# exixe_pogo.net
KiCad netlist of a schematic drawn in EAGLE
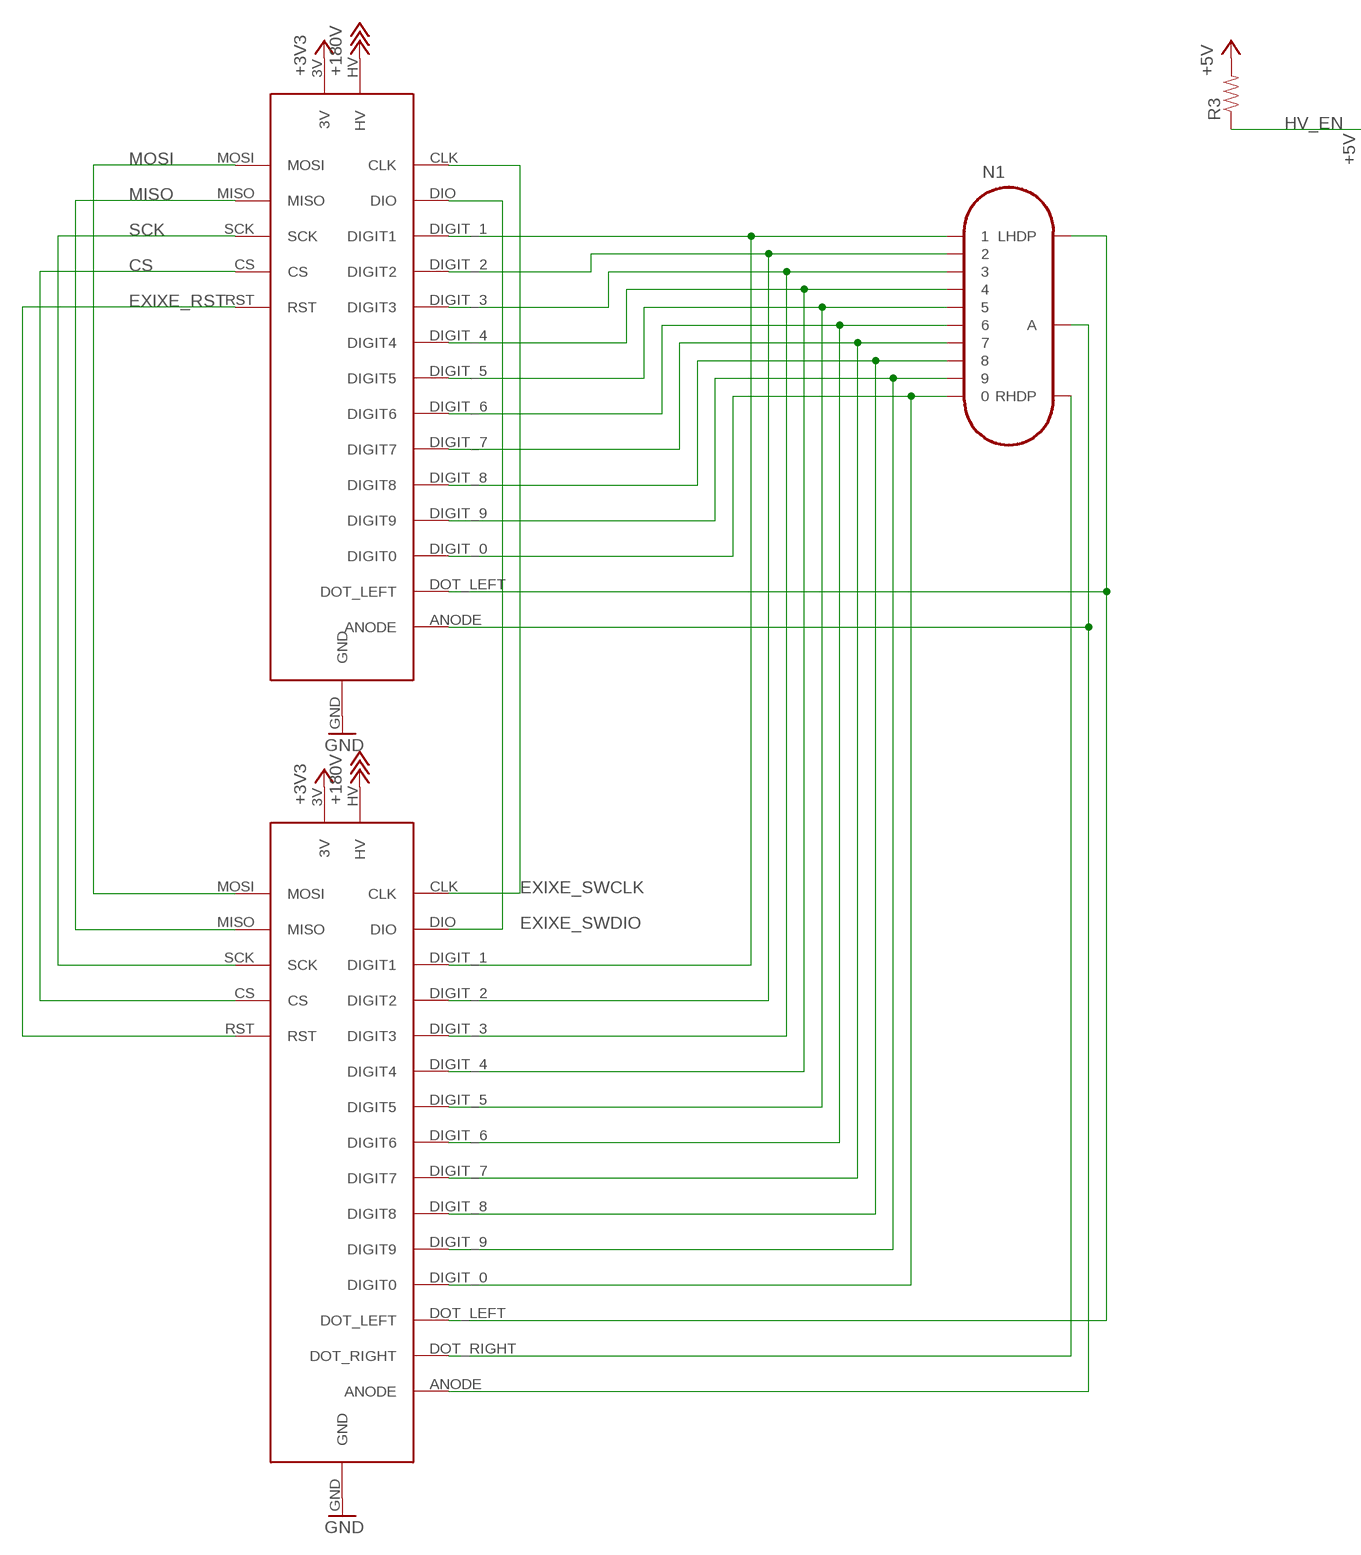
[diagram p0: schematic, sheet 1, part 1 of 2]
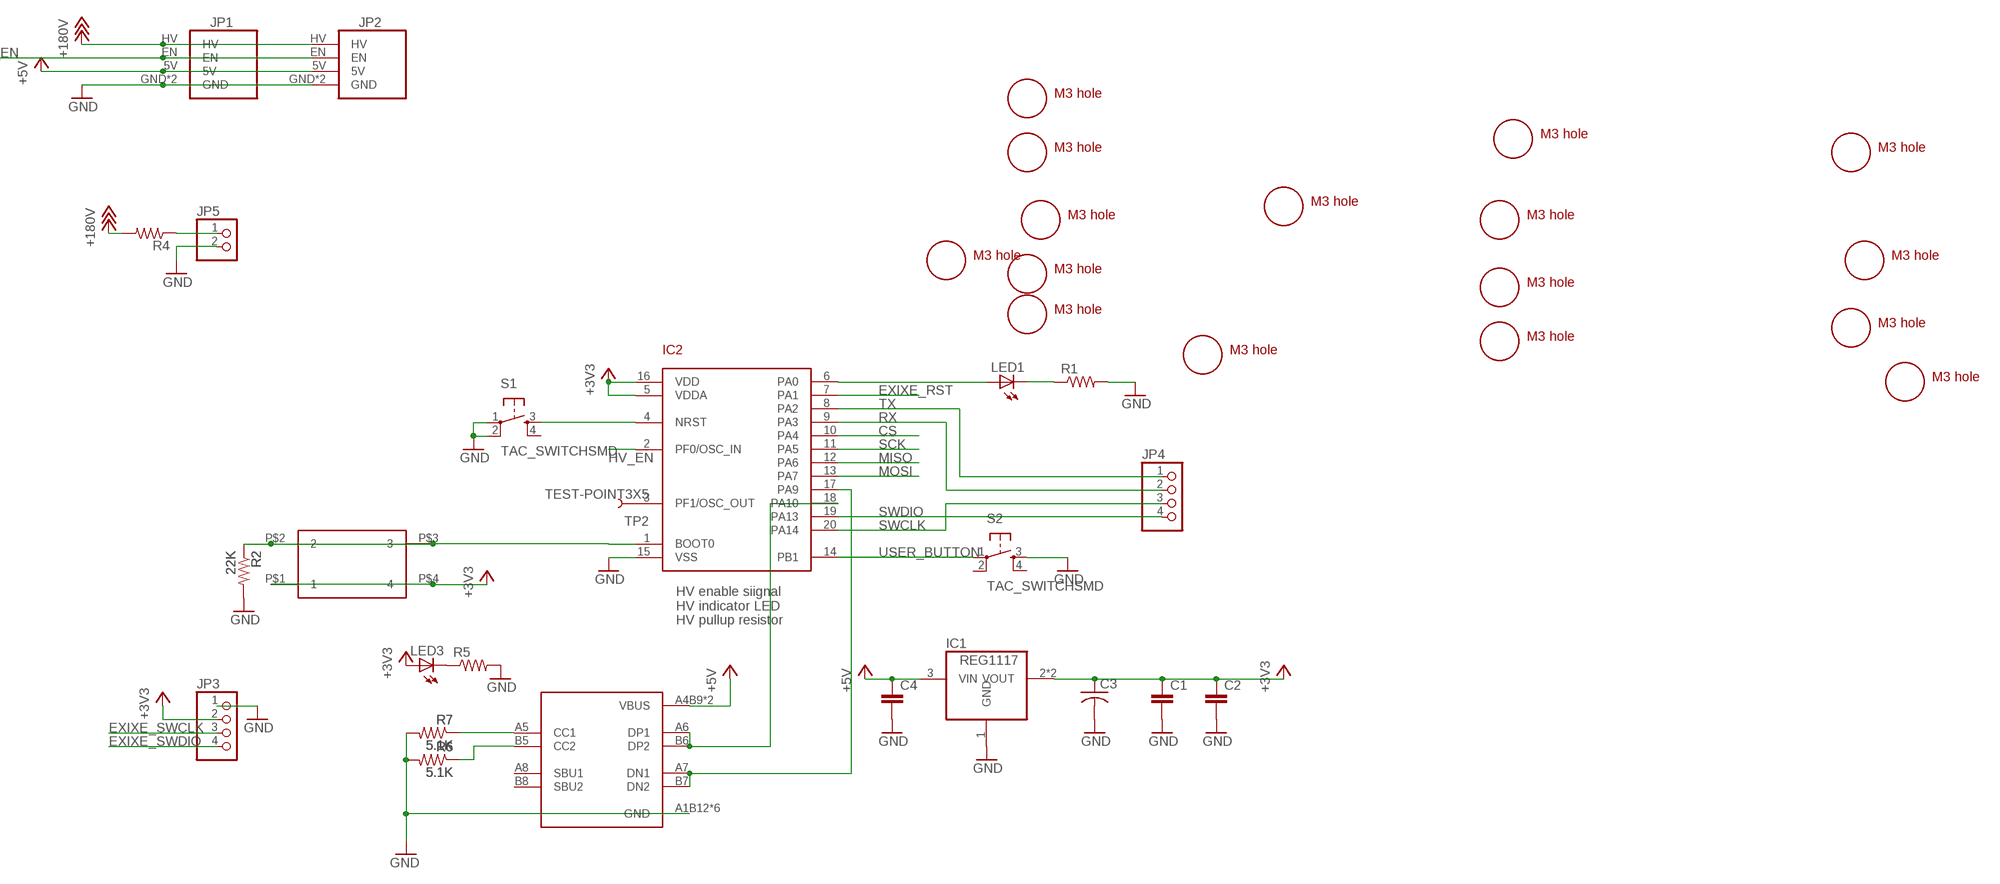
[diagram p1: schematic, sheet 1, part 2 of 2]

(export (version "E")
  (design (tool "Eeschema 10.0.6"))
  (components
    (comp (ref "C1")
      (value "CAP0805")
      (footprint "eagle-import:0805")
      (libsource (lib "eagle-import") (part "CAP0805"))
    )
    (comp (ref "C2")
      (value "CAP0805")
      (footprint "eagle-import:0805")
      (libsource (lib "eagle-import") (part "CAP0805"))
    )
    (comp (ref "C3")
      (value "C-USC1210")
      (footprint "eagle-import:C1210")
      (libsource (lib "eagle-import") (part "C-USC1210"))
    )
    (comp (ref "C4")
      (value "CAP0805")
      (footprint "eagle-import:0805")
      (libsource (lib "eagle-import") (part "CAP0805"))
    )
    (comp (ref "IC1")
      (value "REG1117")
      (footprint "eagle-import:SOT223")
      (libsource (lib "eagle-import") (part "REG1117"))
    )
    (comp (ref "IC2")
      (value "STM32F030F4")
      (footprint "eagle-import:TSSOP20")
      (libsource (lib "eagle-import") (part "STM32F030F4"))
    )
    (comp (ref "JP1")
      (value "EBAY_MODULEEBAY")
      (footprint "eagle-import:EBAY_PKG")
      (libsource (lib "eagle-import") (part "EBAY_MODULEEBAY"))
    )
    (comp (ref "JP2")
      (value "EBAY_MODULETAOBAO")
      (footprint "eagle-import:TAOBAO_PKG")
      (libsource (lib "eagle-import") (part "EBAY_MODULETAOBAO"))
    )
    (comp (ref "JP3")
      (value "PINHD-1X4")
      (footprint "eagle-import:1X04")
      (libsource (lib "eagle-import") (part "PINHD-1X4"))
    )
    (comp (ref "JP4")
      (value "PINHD-1X4")
      (footprint "eagle-import:1X04")
      (libsource (lib "eagle-import") (part "PINHD-1X4"))
    )
    (comp (ref "JP5")
      (value "PINHD-1X2")
      (footprint "eagle-import:1X02")
      (libsource (lib "eagle-import") (part "PINHD-1X2"))
    )
    (comp (ref "LED1")
      (value "LEDCHIP-LED0805")
      (footprint "eagle-import:CHIP-LED0805")
      (libsource (lib "eagle-import") (part "LEDCHIP-LED0805"))
    )
    (comp (ref "LED3")
      (value "LEDCHIP-LED0805")
      (footprint "eagle-import:CHIP-LED0805")
      (libsource (lib "eagle-import") (part "LEDCHIP-LED0805"))
    )
    (comp (ref "N1")
      (value "IN-14")
      (footprint "eagle-import:IN-14")
      (libsource (lib "eagle-import") (part "IN-14"))
    )
    (comp (ref "R1")
      (value "RESISTOR0805-RES")
      (footprint "eagle-import:0805")
      (libsource (lib "eagle-import") (part "RESISTOR0805-RES"))
    )
    (comp (ref "R2")
      (value "22K")
      (footprint "eagle-import:0805")
      (libsource (lib "eagle-import") (part "joyAnalog_RESISTOR0805-RES"))
    )
    (comp (ref "R3")
      (value "RESISTOR0805-RES")
      (footprint "eagle-import:0805")
      (libsource (lib "eagle-import") (part "RESISTOR0805-RES"))
    )
    (comp (ref "R4")
      (value "RESISTOR0805-RES")
      (footprint "eagle-import:0805")
      (libsource (lib "eagle-import") (part "RESISTOR0805-RES"))
    )
    (comp (ref "R5")
      (value "RESISTOR0805-RES")
      (footprint "eagle-import:0805")
      (libsource (lib "eagle-import") (part "RESISTOR0805-RES"))
    )
    (comp (ref "R6")
      (value "5.1K")
      (footprint "eagle-import:0805")
      (libsource (lib "eagle-import") (part "joyAnalog_RESISTOR0805-RES"))
    )
    (comp (ref "R7")
      (value "5.1K")
      (footprint "eagle-import:0805")
      (libsource (lib "eagle-import") (part "joyAnalog_RESISTOR0805-RES"))
    )
    (comp (ref "S1")
      (value "TAC_SWITCHSMD")
      (footprint "eagle-import:TACTILE-SWITCH-SMD")
      (libsource (lib "eagle-import") (part "TAC_SWITCHSMD"))
    )
    (comp (ref "S2")
      (value "TAC_SWITCHSMD")
      (footprint "eagle-import:TACTILE-SWITCH-SMD")
      (libsource (lib "eagle-import") (part "TAC_SWITCHSMD"))
    )
    (comp (ref "SW2")
      (value "324_SW324_SWITCH_FOOT_HOLE")
      (footprint "eagle-import:342_SWICH_FOOT_HOLE")
      (libsource (lib "eagle-import") (part "324_SW324_SWITCH_FOOT_HOLE"))
    )
    (comp (ref "TP2")
      (value "TEST-POINT3X5")
      (footprint "eagle-import:PAD.03X.05")
      (libsource (lib "eagle-import") (part "TEST-POINT3X5"))
    )
    (comp (ref "U$1")
      (value "EXIXE12_POGO")
      (footprint "eagle-import:EXIXE12_PAC")
      (libsource (lib "eagle-import") (part "EXIXE12_POGO"))
    )
    (comp (ref "U$2")
      (value "EXIXE14_POGO")
      (footprint "eagle-import:EXIXE14_PAC")
      (libsource (lib "eagle-import") (part "EXIXE14_POGO"))
    )
    (comp (ref "U$3")
      (value "M3_MOUNTING_HOLE")
      (footprint "eagle-import:M3_MOUNTING_HOLE_PACK")
      (libsource (lib "eagle-import") (part "M3_MOUNTING_HOLE"))
    )
    (comp (ref "U$4")
      (value "M3_MOUNTING_HOLE")
      (footprint "eagle-import:M3_MOUNTING_HOLE_PACK")
      (libsource (lib "eagle-import") (part "M3_MOUNTING_HOLE"))
    )
    (comp (ref "U$5")
      (value "M3_MOUNTING_HOLE")
      (footprint "eagle-import:M3_MOUNTING_HOLE_PACK")
      (libsource (lib "eagle-import") (part "M3_MOUNTING_HOLE"))
    )
    (comp (ref "U$6")
      (value "M3_MOUNTING_HOLE")
      (footprint "eagle-import:M3_MOUNTING_HOLE_PACK")
      (libsource (lib "eagle-import") (part "M3_MOUNTING_HOLE"))
    )
    (comp (ref "U$7")
      (value "M3_MOUNTING_HOLE")
      (footprint "eagle-import:M3_MOUNTING_HOLE_PACK")
      (libsource (lib "eagle-import") (part "M3_MOUNTING_HOLE"))
    )
    (comp (ref "U$8")
      (value "M3_MOUNTING_HOLE")
      (footprint "eagle-import:M3_MOUNTING_HOLE_PACK")
      (libsource (lib "eagle-import") (part "M3_MOUNTING_HOLE"))
    )
    (comp (ref "U$9")
      (value "M3_MOUNTING_HOLE")
      (footprint "eagle-import:M3_MOUNTING_HOLE_PACK")
      (libsource (lib "eagle-import") (part "M3_MOUNTING_HOLE"))
    )
    (comp (ref "U$10")
      (value "M3_MOUNTING_HOLE")
      (footprint "eagle-import:M3_MOUNTING_HOLE_PACK")
      (libsource (lib "eagle-import") (part "M3_MOUNTING_HOLE"))
    )
    (comp (ref "U$11")
      (value "M3_MOUNTING_HOLE")
      (footprint "eagle-import:M3_MOUNTING_HOLE_PACK")
      (libsource (lib "eagle-import") (part "M3_MOUNTING_HOLE"))
    )
    (comp (ref "U$12")
      (value "M3_MOUNTING_HOLE")
      (footprint "eagle-import:M3_MOUNTING_HOLE_PACK")
      (libsource (lib "eagle-import") (part "M3_MOUNTING_HOLE"))
    )
    (comp (ref "U$13")
      (value "M3_MOUNTING_HOLE")
      (footprint "eagle-import:M3_MOUNTING_HOLE_PACK")
      (libsource (lib "eagle-import") (part "M3_MOUNTING_HOLE"))
    )
    (comp (ref "U$14")
      (value "M3_MOUNTING_HOLE")
      (footprint "eagle-import:M3_MOUNTING_HOLE_PACK")
      (libsource (lib "eagle-import") (part "M3_MOUNTING_HOLE"))
    )
    (comp (ref "U$15")
      (value "M3_MOUNTING_HOLE")
      (footprint "eagle-import:M3_MOUNTING_HOLE_PACK")
      (libsource (lib "eagle-import") (part "M3_MOUNTING_HOLE"))
    )
    (comp (ref "U$16")
      (value "M3_MOUNTING_HOLE")
      (footprint "eagle-import:M3_MOUNTING_HOLE_PACK")
      (libsource (lib "eagle-import") (part "M3_MOUNTING_HOLE"))
    )
    (comp (ref "U$17")
      (value "M3_MOUNTING_HOLE")
      (footprint "eagle-import:M3_MOUNTING_HOLE_PACK")
      (libsource (lib "eagle-import") (part "M3_MOUNTING_HOLE"))
    )
    (comp (ref "U$18")
      (value "M3_MOUNTING_HOLE")
      (footprint "eagle-import:M3_MOUNTING_HOLE_PACK")
      (libsource (lib "eagle-import") (part "M3_MOUNTING_HOLE"))
    )
    (comp (ref "U1")
      (value "USBC_16P_CENTERED")
      (footprint "eagle-import:USBC_16P_FOOT")
      (libsource (lib "eagle-import") (part "USBC_16P_CENTERED"))
    )
  )
  (nets
    (net (code "1") (name "+3V3") (class "Default")
      (node (ref "C1") (pin "1") (pinfunction "1_1") (pintype "passive"))
      (node (ref "C2") (pin "1") (pinfunction "1_1") (pintype "passive"))
      (node (ref "C3") (pin "1") (pinfunction "1_1") (pintype "passive"))
      (node (ref "IC1") (pin "2") (pinfunction "VOUT_2") (pintype "output"))
      (node (ref "IC1") (pin "4") (pinfunction "VOUT_4") (pintype "output"))
      (node (ref "IC2") (pin "16") (pinfunction "VDD_16") (pintype "bidirectional"))
      (node (ref "IC2") (pin "5") (pinfunction "VDDA_5") (pintype "bidirectional"))
      (node (ref "JP3") (pin "2") (pinfunction "2_2") (pintype "passive"))
      (node (ref "LED3") (pin "A") (pinfunction "A_A") (pintype "passive"))
      (node (ref "SW2") (pin "P$1") (pinfunction "1_P$1") (pintype "bidirectional"))
      (node (ref "SW2") (pin "P$4") (pinfunction "4_P$4") (pintype "bidirectional"))
      (node (ref "U$1") (pin "3V") (pinfunction "3V_3V") (pintype "bidirectional"))
      (node (ref "U$2") (pin "3V") (pinfunction "3V_3V") (pintype "bidirectional"))
    )
    (net (code "2") (name "+5V") (class "Default")
      (node (ref "C4") (pin "1") (pinfunction "1_1") (pintype "passive"))
      (node (ref "IC1") (pin "3") (pinfunction "VIN_3") (pintype "input"))
      (node (ref "JP1") (pin "5V") (pinfunction "5V_5V") (pintype "bidirectional"))
      (node (ref "JP2") (pin "5V") (pinfunction "5V_5V") (pintype "bidirectional"))
      (node (ref "R3") (pin "2") (pinfunction "2_2") (pintype "passive"))
      (node (ref "U1") (pin "A4B9") (pinfunction "VBUS_A4B9") (pintype "bidirectional"))
      (node (ref "U1") (pin "B4A9") (pinfunction "VBUS_B4A9") (pintype "bidirectional"))
    )
    (net (code "3") (name "+180V") (class "Default")
      (node (ref "JP1") (pin "HV") (pinfunction "HV_HV") (pintype "bidirectional"))
      (node (ref "JP2") (pin "HV") (pinfunction "HV_HV") (pintype "bidirectional"))
      (node (ref "R4") (pin "2") (pinfunction "2_2") (pintype "passive"))
      (node (ref "U$1") (pin "HV") (pinfunction "HV_HV") (pintype "bidirectional"))
      (node (ref "U$2") (pin "HV") (pinfunction "HV_HV") (pintype "bidirectional"))
    )
    (net (code "4") (name "/CS") (class "Default")
      (node (ref "IC2") (pin "10") (pinfunction "PA4_10") (pintype "bidirectional"))
      (node (ref "U$1") (pin "CS") (pinfunction "CS_CS") (pintype "bidirectional"))
      (node (ref "U$2") (pin "CS") (pinfunction "CS_CS") (pintype "bidirectional"))
    )
    (net (code "5") (name "/EXIXE_RST") (class "Default")
      (node (ref "IC2") (pin "7") (pinfunction "PA1_7") (pintype "bidirectional"))
      (node (ref "U$1") (pin "RST") (pinfunction "RST_RST") (pintype "bidirectional"))
      (node (ref "U$2") (pin "RST") (pinfunction "RST_RST") (pintype "bidirectional"))
    )
    (net (code "6") (name "/EXIXE_SWCLK") (class "Default")
      (node (ref "JP3") (pin "3") (pinfunction "3_3") (pintype "passive"))
      (node (ref "U$1") (pin "CLK") (pinfunction "CLK_CLK") (pintype "bidirectional"))
      (node (ref "U$2") (pin "CLK") (pinfunction "CLK_CLK") (pintype "bidirectional"))
    )
    (net (code "7") (name "/EXIXE_SWDIO") (class "Default")
      (node (ref "JP3") (pin "4") (pinfunction "4_4") (pintype "passive"))
      (node (ref "U$1") (pin "DIO") (pinfunction "DIO_DIO") (pintype "bidirectional"))
      (node (ref "U$2") (pin "DIO") (pinfunction "DIO_DIO") (pintype "bidirectional"))
    )
    (net (code "8") (name "/HV_EN") (class "Default")
      (node (ref "IC2") (pin "2") (pinfunction "PF0/OSC_IN_2") (pintype "bidirectional"))
      (node (ref "JP1") (pin "EN") (pinfunction "EN_EN") (pintype "bidirectional"))
      (node (ref "JP2") (pin "EN") (pinfunction "EN_EN") (pintype "bidirectional"))
      (node (ref "R3") (pin "1") (pinfunction "1_1") (pintype "passive"))
    )
    (net (code "9") (name "/MISO") (class "Default")
      (node (ref "IC2") (pin "12") (pinfunction "PA6_12") (pintype "bidirectional"))
      (node (ref "U$1") (pin "MISO") (pinfunction "MISO_MISO") (pintype "bidirectional"))
      (node (ref "U$2") (pin "MISO") (pinfunction "MISO_MISO") (pintype "bidirectional"))
    )
    (net (code "10") (name "/MOSI") (class "Default")
      (node (ref "IC2") (pin "13") (pinfunction "PA7_13") (pintype "bidirectional"))
      (node (ref "U$1") (pin "MOSI") (pinfunction "MOSI_MOSI") (pintype "bidirectional"))
      (node (ref "U$2") (pin "MOSI") (pinfunction "MOSI_MOSI") (pintype "bidirectional"))
    )
    (net (code "11") (name "/RX") (class "Default")
      (node (ref "IC2") (pin "9") (pinfunction "PA3_9") (pintype "bidirectional"))
      (node (ref "JP4") (pin "2") (pinfunction "2_2") (pintype "passive"))
    )
    (net (code "12") (name "/SCK") (class "Default")
      (node (ref "IC2") (pin "11") (pinfunction "PA5_11") (pintype "bidirectional"))
      (node (ref "U$1") (pin "SCK") (pinfunction "SCK_SCK") (pintype "bidirectional"))
      (node (ref "U$2") (pin "SCK") (pinfunction "SCK_SCK") (pintype "bidirectional"))
    )
    (net (code "13") (name "/SWCLK") (class "Default")
      (node (ref "IC2") (pin "20") (pinfunction "PA14_20") (pintype "bidirectional"))
      (node (ref "JP4") (pin "3") (pinfunction "3_3") (pintype "passive"))
    )
    (net (code "14") (name "/SWDIO") (class "Default")
      (node (ref "IC2") (pin "19") (pinfunction "PA13_19") (pintype "bidirectional"))
      (node (ref "JP4") (pin "4") (pinfunction "4_4") (pintype "passive"))
    )
    (net (code "15") (name "/TX") (class "Default")
      (node (ref "IC2") (pin "8") (pinfunction "PA2_8") (pintype "bidirectional"))
      (node (ref "JP4") (pin "1") (pinfunction "1_1") (pintype "passive"))
    )
    (net (code "16") (name "/USER_BUTTON") (class "Default")
      (node (ref "IC2") (pin "14") (pinfunction "PB1_14") (pintype "bidirectional"))
      (node (ref "S2") (pin "1") (pinfunction "1_1") (pintype "passive"))
    )
    (net (code "17") (name "GND") (class "Default")
      (node (ref "C1") (pin "2") (pinfunction "2_2") (pintype "passive"))
      (node (ref "C2") (pin "2") (pinfunction "2_2") (pintype "passive"))
      (node (ref "C3") (pin "2") (pinfunction "2_2") (pintype "passive"))
      (node (ref "C4") (pin "2") (pinfunction "2_2") (pintype "passive"))
      (node (ref "IC1") (pin "1") (pinfunction "GND_1") (pintype "power_in"))
      (node (ref "IC2") (pin "15") (pinfunction "VSS_15") (pintype "bidirectional"))
      (node (ref "JP1") (pin "GND") (pinfunction "GND_GND") (pintype "bidirectional"))
      (node (ref "JP1") (pin "GND2") (pinfunction "GND_GND2") (pintype "bidirectional"))
      (node (ref "JP2") (pin "GND") (pinfunction "GND_GND") (pintype "bidirectional"))
      (node (ref "JP2") (pin "GND2") (pinfunction "GND_GND2") (pintype "bidirectional"))
      (node (ref "JP3") (pin "1") (pinfunction "1_1") (pintype "passive"))
      (node (ref "JP5") (pin "2") (pinfunction "2_2") (pintype "passive"))
      (node (ref "R1") (pin "2") (pinfunction "2_2") (pintype "passive"))
      (node (ref "R2") (pin "2") (pinfunction "2_2") (pintype "passive"))
      (node (ref "R5") (pin "2") (pinfunction "2_2") (pintype "passive"))
      (node (ref "R6") (pin "2") (pinfunction "2_2") (pintype "passive"))
      (node (ref "R7") (pin "2") (pinfunction "2_2") (pintype "passive"))
      (node (ref "S1") (pin "1") (pinfunction "1_1") (pintype "passive"))
      (node (ref "S1") (pin "2") (pinfunction "2_2") (pintype "passive"))
      (node (ref "S2") (pin "3") (pinfunction "3_3") (pintype "passive"))
      (node (ref "U$1") (pin "GND") (pinfunction "GND_GND") (pintype "bidirectional"))
      (node (ref "U$2") (pin "GND") (pinfunction "GND_GND") (pintype "bidirectional"))
      (node (ref "U1") (pin "A1B12") (pinfunction "GND_A1B12") (pintype "bidirectional"))
      (node (ref "U1") (pin "B11A12") (pinfunction "GND_B11A12") (pintype "bidirectional"))
      (node (ref "U1") (pin "P$13") (pinfunction "GND_P$13") (pintype "bidirectional"))
      (node (ref "U1") (pin "P$14") (pinfunction "GND_P$14") (pintype "bidirectional"))
      (node (ref "U1") (pin "P$15") (pinfunction "GND_P$15") (pintype "bidirectional"))
      (node (ref "U1") (pin "P$16") (pinfunction "GND_P$16") (pintype "bidirectional"))
    )
    (net (code "18") (name "Net-(IC2-BOOT0)") (class "Default")
      (node (ref "IC2") (pin "1") (pinfunction "BOOT0_1") (pintype "bidirectional"))
      (node (ref "R2") (pin "1") (pinfunction "1_1") (pintype "passive"))
      (node (ref "SW2") (pin "P$2") (pinfunction "2_P$2") (pintype "bidirectional"))
      (node (ref "SW2") (pin "P$3") (pinfunction "3_P$3") (pintype "bidirectional"))
    )
    (net (code "19") (name "Net-(IC2-NRST)") (class "Default")
      (node (ref "IC2") (pin "4") (pinfunction "NRST_4") (pintype "bidirectional"))
      (node (ref "S1") (pin "3") (pinfunction "3_3") (pintype "passive"))
    )
    (net (code "20") (name "Net-(IC2-PA0)") (class "Default")
      (node (ref "IC2") (pin "6") (pinfunction "PA0_6") (pintype "bidirectional"))
      (node (ref "LED1") (pin "A") (pinfunction "A_A") (pintype "passive"))
    )
    (net (code "21") (name "Net-(IC2-PA9)") (class "Default")
      (node (ref "IC2") (pin "17") (pinfunction "PA9_17") (pintype "bidirectional"))
      (node (ref "U1") (pin "A7") (pinfunction "DN1_A7") (pintype "bidirectional"))
      (node (ref "U1") (pin "B7") (pinfunction "DN2_B7") (pintype "bidirectional"))
    )
    (net (code "22") (name "Net-(IC2-PA10)") (class "Default")
      (node (ref "IC2") (pin "18") (pinfunction "PA10_18") (pintype "bidirectional"))
      (node (ref "U1") (pin "A6") (pinfunction "DP1_A6") (pintype "bidirectional"))
      (node (ref "U1") (pin "B6") (pinfunction "DP2_B6") (pintype "bidirectional"))
    )
    (net (code "23") (name "Net-(IC2-PF1{slash}OSC_OUT)") (class "Default")
      (node (ref "IC2") (pin "3") (pinfunction "PF1/OSC_OUT_3") (pintype "bidirectional"))
      (node (ref "TP2") (pin "P$1") (pinfunction "1_P$1") (pintype "bidirectional"))
    )
    (net (code "24") (name "Net-(JP5-Pad1)") (class "Default")
      (node (ref "JP5") (pin "1") (pinfunction "1_1") (pintype "passive"))
      (node (ref "R4") (pin "1") (pinfunction "1_1") (pintype "passive"))
    )
    (net (code "25") (name "Net-(LED1-PadC)") (class "Default")
      (node (ref "LED1") (pin "C") (pinfunction "C_C") (pintype "passive"))
      (node (ref "R1") (pin "1") (pinfunction "1_1") (pintype "passive"))
    )
    (net (code "26") (name "Net-(LED3-PadC)") (class "Default")
      (node (ref "LED3") (pin "C") (pinfunction "C_C") (pintype "passive"))
      (node (ref "R5") (pin "1") (pinfunction "1_1") (pintype "passive"))
    )
    (net (code "27") (name "Net-(N1-PadA)") (class "Default")
      (node (ref "N1") (pin "A") (pinfunction "A_A") (pintype "bidirectional"))
      (node (ref "U$1") (pin "ANODE") (pinfunction "ANODE_ANODE") (pintype "bidirectional"))
      (node (ref "U$2") (pin "ANODE") (pinfunction "ANODE_ANODE") (pintype "bidirectional"))
    )
    (net (code "28") (name "Net-(N1-PadLHDP)") (class "Default")
      (node (ref "N1") (pin "LHDP") (pinfunction "LHDP_LHDP") (pintype "bidirectional"))
      (node (ref "U$1") (pin "DOT_LEFT") (pinfunction "DOT_LEFT_DOT_LEFT") (pintype "bidirectional"))
      (node (ref "U$2") (pin "DOT_LEFT") (pinfunction "DOT_LEFT_DOT_LEFT") (pintype "bidirectional"))
    )
    (net (code "29") (name "Net-(N1-PadRHDP)") (class "Default")
      (node (ref "N1") (pin "RHDP") (pinfunction "RHDP_RHDP") (pintype "bidirectional"))
      (node (ref "U$2") (pin "DOT_RIGHT") (pinfunction "DOT_RIGHT_DOT_RIGHT") (pintype "bidirectional"))
    )
    (net (code "30") (name "Net-(U$1-DIGIT0)") (class "Default")
      (node (ref "N1") (pin "0") (pinfunction "0_0") (pintype "bidirectional"))
      (node (ref "U$1") (pin "DIGIT_0") (pinfunction "DIGIT0_DIGIT_0") (pintype "bidirectional"))
      (node (ref "U$2") (pin "DIGIT_0") (pinfunction "DIGIT0_DIGIT_0") (pintype "bidirectional"))
    )
    (net (code "31") (name "Net-(U$1-DIGIT1)") (class "Default")
      (node (ref "N1") (pin "1") (pinfunction "1_1") (pintype "bidirectional"))
      (node (ref "U$1") (pin "DIGIT_1") (pinfunction "DIGIT1_DIGIT_1") (pintype "bidirectional"))
      (node (ref "U$2") (pin "DIGIT_1") (pinfunction "DIGIT1_DIGIT_1") (pintype "bidirectional"))
    )
    (net (code "32") (name "Net-(U$1-DIGIT2)") (class "Default")
      (node (ref "N1") (pin "2") (pinfunction "2_2") (pintype "bidirectional"))
      (node (ref "U$1") (pin "DIGIT_2") (pinfunction "DIGIT2_DIGIT_2") (pintype "bidirectional"))
      (node (ref "U$2") (pin "DIGIT_2") (pinfunction "DIGIT2_DIGIT_2") (pintype "bidirectional"))
    )
    (net (code "33") (name "Net-(U$1-DIGIT3)") (class "Default")
      (node (ref "N1") (pin "3") (pinfunction "3_3") (pintype "bidirectional"))
      (node (ref "U$1") (pin "DIGIT_3") (pinfunction "DIGIT3_DIGIT_3") (pintype "bidirectional"))
      (node (ref "U$2") (pin "DIGIT_3") (pinfunction "DIGIT3_DIGIT_3") (pintype "bidirectional"))
    )
    (net (code "34") (name "Net-(U$1-DIGIT4)") (class "Default")
      (node (ref "N1") (pin "4") (pinfunction "4_4") (pintype "bidirectional"))
      (node (ref "U$1") (pin "DIGIT_4") (pinfunction "DIGIT4_DIGIT_4") (pintype "bidirectional"))
      (node (ref "U$2") (pin "DIGIT_4") (pinfunction "DIGIT4_DIGIT_4") (pintype "bidirectional"))
    )
    (net (code "35") (name "Net-(U$1-DIGIT5)") (class "Default")
      (node (ref "N1") (pin "5") (pinfunction "5_5") (pintype "bidirectional"))
      (node (ref "U$1") (pin "DIGIT_5") (pinfunction "DIGIT5_DIGIT_5") (pintype "bidirectional"))
      (node (ref "U$2") (pin "DIGIT_5") (pinfunction "DIGIT5_DIGIT_5") (pintype "bidirectional"))
    )
    (net (code "36") (name "Net-(U$1-DIGIT6)") (class "Default")
      (node (ref "N1") (pin "6") (pinfunction "6_6") (pintype "bidirectional"))
      (node (ref "U$1") (pin "DIGIT_6") (pinfunction "DIGIT6_DIGIT_6") (pintype "bidirectional"))
      (node (ref "U$2") (pin "DIGIT_6") (pinfunction "DIGIT6_DIGIT_6") (pintype "bidirectional"))
    )
    (net (code "37") (name "Net-(U$1-DIGIT7)") (class "Default")
      (node (ref "N1") (pin "7") (pinfunction "7_7") (pintype "bidirectional"))
      (node (ref "U$1") (pin "DIGIT_7") (pinfunction "DIGIT7_DIGIT_7") (pintype "bidirectional"))
      (node (ref "U$2") (pin "DIGIT_7") (pinfunction "DIGIT7_DIGIT_7") (pintype "bidirectional"))
    )
    (net (code "38") (name "Net-(U$1-DIGIT8)") (class "Default")
      (node (ref "N1") (pin "8") (pinfunction "8_8") (pintype "bidirectional"))
      (node (ref "U$1") (pin "DIGIT_8") (pinfunction "DIGIT8_DIGIT_8") (pintype "bidirectional"))
      (node (ref "U$2") (pin "DIGIT_8") (pinfunction "DIGIT8_DIGIT_8") (pintype "bidirectional"))
    )
    (net (code "39") (name "Net-(U$1-DIGIT9)") (class "Default")
      (node (ref "N1") (pin "9") (pinfunction "9_9") (pintype "bidirectional"))
      (node (ref "U$1") (pin "DIGIT_9") (pinfunction "DIGIT9_DIGIT_9") (pintype "bidirectional"))
      (node (ref "U$2") (pin "DIGIT_9") (pinfunction "DIGIT9_DIGIT_9") (pintype "bidirectional"))
    )
    (net (code "40") (name "Net-(U1-CC1)") (class "Default")
      (node (ref "R7") (pin "1") (pinfunction "1_1") (pintype "passive"))
      (node (ref "U1") (pin "A5") (pinfunction "CC1_A5") (pintype "bidirectional"))
    )
    (net (code "41") (name "Net-(U1-CC2)") (class "Default")
      (node (ref "R6") (pin "1") (pinfunction "1_1") (pintype "passive"))
      (node (ref "U1") (pin "B5") (pinfunction "CC2_B5") (pintype "bidirectional"))
    )
    (net (code "42") (name "unconnected-(S1-Pad4)") (class "Default")
      (node (ref "S1") (pin "4") (pinfunction "4_4") (pintype "passive"))
    )
    (net (code "43") (name "unconnected-(S2-Pad2)") (class "Default")
      (node (ref "S2") (pin "2") (pinfunction "2_2") (pintype "passive"))
    )
    (net (code "44") (name "unconnected-(S2-Pad4)") (class "Default")
      (node (ref "S2") (pin "4") (pinfunction "4_4") (pintype "passive"))
    )
    (net (code "45") (name "unconnected-(U1-SBU1-PadA8)") (class "Default")
      (node (ref "U1") (pin "A8") (pinfunction "SBU1_A8") (pintype "bidirectional"))
    )
    (net (code "46") (name "unconnected-(U1-SBU2-PadB8)") (class "Default")
      (node (ref "U1") (pin "B8") (pinfunction "SBU2_B8") (pintype "bidirectional"))
    )
  )
)
